# Sheet1.net
KiCad netlist of a schematic drawn in Altium Designer
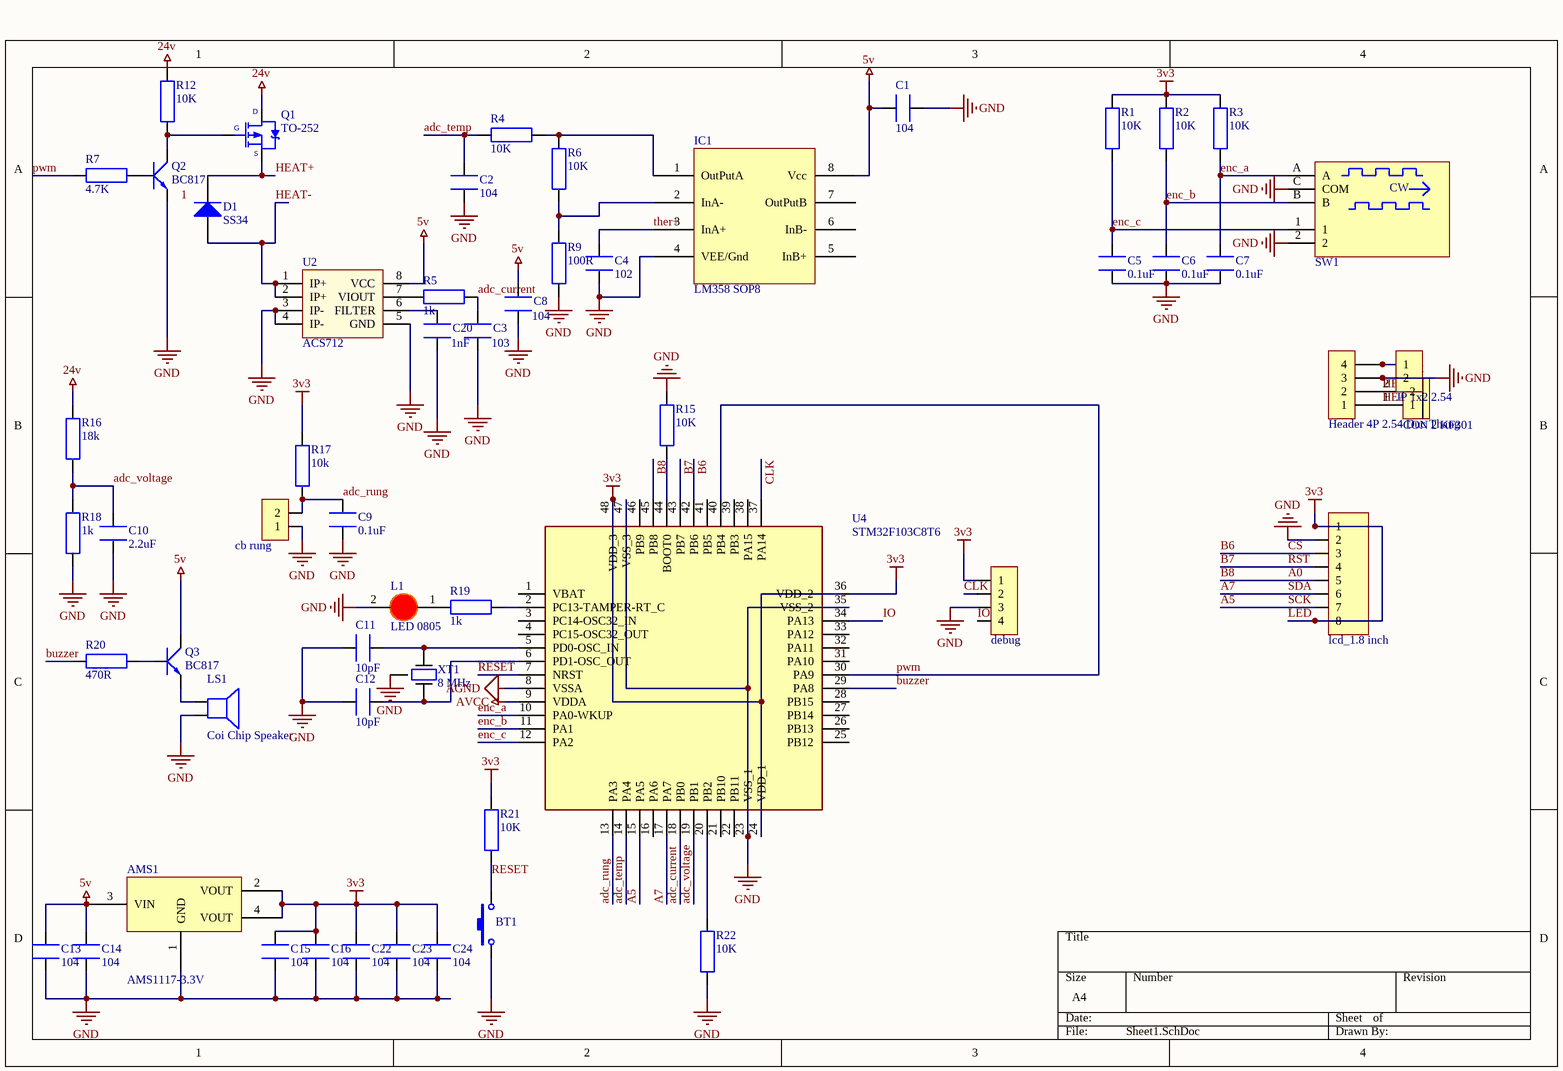
[diagram p0: Sheet1.SchDoc]

(export (version "E")
  (design (tool "Eeschema 10.0.6"))
  (components
    (comp (ref "AMS1")
      (value "AMS1117-3.3V")
      (footprint "SOT223")
      (description "Dán")
      (libsource (lib "Altium_Lib_by_KhueNguyenCreator") (part "AMS1117 SMD"))
    )
    (comp (ref "BT1")
      (value "Nut Nhan 2 Chan SMD 3x6x2.5")
      (footprint "Nut Nhan 2 Chan SMD 3x6x2.5")
      (libsource (lib "Altium_Lib_by_KhueNguyenCreator") (part "Nut Nhan 2 Chan SMD 3x6x2.5"))
    )
    (comp (ref "C1")
      (value "104")
      (footprint "CAPC1608X09L")
      (description "CAP CER 0.1UF 50V X7R 0603")
      (fields
        (field (name "MANUFACTURER") "Murata Electronics North America")
        (field (name "MANUFACTURER PART NUMBER") "GRM188R71H104KA93D")
      )
      (libsource (lib "two_ax_PCB") (part "GRM188R71H104KA93D"))
    )
    (comp (ref "C2")
      (value "104")
      (footprint "CAPC1608X09L")
      (description "CAP CER 0.1UF 50V X7R 0603")
      (fields
        (field (name "MANUFACTURER") "Murata Electronics North America")
        (field (name "MANUFACTURER PART NUMBER") "GRM188R71H104KA93D")
      )
      (libsource (lib "two_ax_PCB") (part "GRM188R71H104KA93D"))
    )
    (comp (ref "C3")
      (value "103")
      (footprint "CAPC1608X09L")
      (description "CAP CER 0.1UF 50V X7R 0603")
      (fields
        (field (name "MANUFACTURER") "Murata Electronics North America")
        (field (name "MANUFACTURER PART NUMBER") "GRM188R71H104KA93D")
      )
      (libsource (lib "two_ax_PCB") (part "GRM188R71H104KA93D"))
    )
    (comp (ref "C4")
      (value "102")
      (footprint "CAPC1608X09L")
      (description "CAP CER 0.1UF 50V X7R 0603")
      (fields
        (field (name "MANUFACTURER") "Murata Electronics North America")
        (field (name "MANUFACTURER PART NUMBER") "GRM188R71H104KA93D")
      )
      (libsource (lib "two_ax_PCB") (part "GRM188R71H104KA93D"))
    )
    (comp (ref "C5")
      (value "0.1uF")
      (footprint "CAPC1608X09L")
      (description "CAP CER 0.1UF 50V X7R 0603")
      (fields
        (field (name "MANUFACTURER") "Murata Electronics North America")
        (field (name "MANUFACTURER PART NUMBER") "GRM188R71H104KA93D")
      )
      (libsource (lib "two_ax_PCB") (part "GRM188R71H104KA93D"))
    )
    (comp (ref "C6")
      (value "0.1uF")
      (footprint "CAPC1608X09L")
      (description "CAP CER 0.1UF 50V X7R 0603")
      (fields
        (field (name "MANUFACTURER") "Murata Electronics North America")
        (field (name "MANUFACTURER PART NUMBER") "GRM188R71H104KA93D")
      )
      (libsource (lib "two_ax_PCB") (part "GRM188R71H104KA93D"))
    )
    (comp (ref "C7")
      (value "0.1uF")
      (footprint "CAPC1608X09L")
      (description "CAP CER 0.1UF 50V X7R 0603")
      (fields
        (field (name "MANUFACTURER") "Murata Electronics North America")
        (field (name "MANUFACTURER PART NUMBER") "GRM188R71H104KA93D")
      )
      (libsource (lib "two_ax_PCB") (part "GRM188R71H104KA93D"))
    )
    (comp (ref "C8")
      (value "104")
      (footprint "CAPC1608X09L")
      (description "CAP CER 0.1UF 50V X7R 0603")
      (fields
        (field (name "MANUFACTURER") "Murata Electronics North America")
        (field (name "MANUFACTURER PART NUMBER") "GRM188R71H104KA93D")
      )
      (libsource (lib "two_ax_PCB") (part "GRM188R71H104KA93D"))
    )
    (comp (ref "C9")
      (value "0.1uF")
      (footprint "CAPC1608X09L")
      (description "CAP CER 0.1UF 50V X7R 0603")
      (fields
        (field (name "MANUFACTURER") "Murata Electronics North America")
        (field (name "MANUFACTURER PART NUMBER") "GRM188R71H104KA93D")
      )
      (libsource (lib "two_ax_PCB") (part "GRM188R71H104KA93D"))
    )
    (comp (ref "C10")
      (value "2.2uF")
      (footprint "CAPC1608X09L")
      (description "CAP CER 0.1UF 50V X7R 0603")
      (fields
        (field (name "MANUFACTURER") "Murata Electronics North America")
        (field (name "MANUFACTURER PART NUMBER") "GRM188R71H104KA93D")
      )
      (libsource (lib "two_ax_PCB") (part "GRM188R71H104KA93D"))
    )
    (comp (ref "C11")
      (value "10pF")
      (footprint "CAPC1608X09L")
      (description "CAP CER 0.1UF 50V X7R 0603")
      (fields
        (field (name "MANUFACTURER") "Murata Electronics North America")
        (field (name "MANUFACTURER PART NUMBER") "GRM188R71H104KA93D")
      )
      (libsource (lib "two_ax_PCB") (part "GRM188R71H104KA93D"))
    )
    (comp (ref "C12")
      (value "10pF")
      (footprint "CAPC1608X09L")
      (description "CAP CER 0.1UF 50V X7R 0603")
      (fields
        (field (name "MANUFACTURER") "Murata Electronics North America")
        (field (name "MANUFACTURER PART NUMBER") "GRM188R71H104KA93D")
      )
      (libsource (lib "two_ax_PCB") (part "GRM188R71H104KA93D"))
    )
    (comp (ref "C13")
      (value "104")
      (footprint "CAPC1608X09L")
      (description "CAP CER 0.1UF 50V X7R 0603")
      (fields
        (field (name "MANUFACTURER") "Murata Electronics North America")
        (field (name "MANUFACTURER PART NUMBER") "GRM188R71H104KA93D")
      )
      (libsource (lib "two_ax_PCB") (part "GRM188R71H104KA93D"))
    )
    (comp (ref "C14")
      (value "104")
      (footprint "CAPC1608X09L")
      (description "CAP CER 0.1UF 50V X7R 0603")
      (fields
        (field (name "MANUFACTURER") "Murata Electronics North America")
        (field (name "MANUFACTURER PART NUMBER") "GRM188R71H104KA93D")
      )
      (libsource (lib "two_ax_PCB") (part "GRM188R71H104KA93D"))
    )
    (comp (ref "C15")
      (value "104")
      (footprint "CAPC1608X09L")
      (description "CAP CER 0.1UF 50V X7R 0603")
      (fields
        (field (name "MANUFACTURER") "Murata Electronics North America")
        (field (name "MANUFACTURER PART NUMBER") "GRM188R71H104KA93D")
      )
      (libsource (lib "two_ax_PCB") (part "GRM188R71H104KA93D"))
    )
    (comp (ref "C16")
      (value "104")
      (footprint "CAPC1608X09L")
      (description "CAP CER 0.1UF 50V X7R 0603")
      (fields
        (field (name "MANUFACTURER") "Murata Electronics North America")
        (field (name "MANUFACTURER PART NUMBER") "GRM188R71H104KA93D")
      )
      (libsource (lib "two_ax_PCB") (part "GRM188R71H104KA93D"))
    )
    (comp (ref "C20")
      (value "1nF")
      (footprint "CAPC1608X09L")
      (description "CAP CER 0.1UF 50V X7R 0603")
      (fields
        (field (name "MANUFACTURER") "Murata Electronics North America")
        (field (name "MANUFACTURER PART NUMBER") "GRM188R71H104KA93D")
      )
      (libsource (lib "two_ax_PCB") (part "GRM188R71H104KA93D"))
    )
    (comp (ref "C22")
      (value "104")
      (footprint "CAPC1608X09L")
      (description "CAP CER 0.1UF 50V X7R 0603")
      (fields
        (field (name "MANUFACTURER") "Murata Electronics North America")
        (field (name "MANUFACTURER PART NUMBER") "GRM188R71H104KA93D")
      )
      (libsource (lib "two_ax_PCB") (part "GRM188R71H104KA93D"))
    )
    (comp (ref "C23")
      (value "104")
      (footprint "CAPC1608X09L")
      (description "CAP CER 0.1UF 50V X7R 0603")
      (fields
        (field (name "MANUFACTURER") "Murata Electronics North America")
        (field (name "MANUFACTURER PART NUMBER") "GRM188R71H104KA93D")
      )
      (libsource (lib "two_ax_PCB") (part "GRM188R71H104KA93D"))
    )
    (comp (ref "C24")
      (value "104")
      (footprint "CAPC1608X09L")
      (description "CAP CER 0.1UF 50V X7R 0603")
      (fields
        (field (name "MANUFACTURER") "Murata Electronics North America")
        (field (name "MANUFACTURER PART NUMBER") "GRM188R71H104KA93D")
      )
      (libsource (lib "two_ax_PCB") (part "GRM188R71H104KA93D"))
    )
    (comp (ref "D1")
      (value "SS34")
      (footprint "DIODE SMA")
      (description "Dán")
      (libsource (lib "Altium_Lib_by_KhueNguyenCreator") (part "Diode SS34 ( 1N5822 )"))
    )
    (comp (ref "H1")
      (value "Header 4P 2.54 Duc Thang")
      (footprint "XH2.54M-4")
      (description "Cắm")
      (libsource (lib "Altium_Lib_by_KhueNguyenCreator") (part "Header 4P 2.54 Duc Thang"))
    )
    (comp (ref "IC1")
      (value "LM358 SOP8")
      (footprint "SOP 8")
      (description "Dán")
      (libsource (lib "Altium_Lib_by_KhueNguyenCreator") (part "LM358 SOP8"))
    )
    (comp (ref "JP1")
      (value "debug")
      (footprint "JP 1x4 DT")
      (description "Cắm")
      (libsource (lib "Altium_Lib_by_KhueNguyenCreator") (part "JP 1x4 2.54 Duc Thang"))
    )
    (comp (ref "JP2")
      (value "JP 1x2 2.54")
      (footprint "JP 1x2 DT")
      (description "Cắm")
      (libsource (lib "") (part "JP 1x2 2.54 Duc Thang_1"))
    )
    (comp (ref "JP3")
      (value "cb rung")
      (footprint "JP 1x2 DT")
      (description "Cắm")
      (libsource (lib "Altium_Lib_by_KhueNguyenCreator") (part "JP 1x2 2.54 Duc Thang"))
    )
    (comp (ref "JP4")
      (value "lcd_1.8 inch")
      (footprint "JP 1x8 DT")
      (description "Cắm")
      (libsource (lib "Altium_Lib_by_KhueNguyenCreator") (part "JP 1x8 2.54 Duc Thang"))
    )
    (comp (ref "KF2")
      (value "CON 2 KF301")
      (footprint "Con 2 KF301 5.08")
      (description "Cắm")
      (libsource (lib "Altium_Lib_by_KhueNguyenCreator") (part "CON 2 KF301"))
    )
    (comp (ref "L1")
      (value "LED 0805")
      (footprint "LED-0805-Red")
      (description "Dán")
      (libsource (lib "Altium_Lib_by_KhueNguyenCreator") (part "LED 0805 Do"))
    )
    (comp (ref "LS1")
      (value "Coi Chip Speaker")
      (footprint "Coi Chip Speacker")
      (description "Còi chip")
      (libsource (lib "Altium_Lib_by_KhueNguyenCreator") (part "Coi Chip Speaker"))
    )
    (comp (ref "Q1")
      (value "TO-252")
      (footprint "TO-252-3_L6.6-W6.1-P4.57-LS9.9-BR-CW")
      (description "P-Channel Power MOSFET")
      (fields (field (name "PUBLISHER") "Altium Limited"))
      (libsource (lib "Altium_Lib_by_KhueNguyenCreator") (part "FET AO D409"))
    )
    (comp (ref "Q2")
      (value "BC817")
      (footprint "SOT-23")
      (description "SOT-23 - C8658")
      (libsource (lib "Altium_Lib_by_KhueNguyenCreator") (part "Trans BC817"))
    )
    (comp (ref "Q3")
      (value "BC817")
      (footprint "SOT-23")
      (description "SOT-23 - C8658")
      (libsource (lib "Altium_Lib_by_KhueNguyenCreator") (part "Trans BC817"))
    )
    (comp (ref "R1")
      (value "10K")
      (footprint "RESC1608X55N")
      (description "RES SMD 10K OHM 1% 1/10W 0603")
      (fields
        (field (name "MANUFACTURER") "Yageo")
        (field (name "MANUFACTURER PART NUMBER") "RC0603FR-0710KL")
      )
      (libsource (lib "two_ax_PCB") (part "RC0603FR-0710KL"))
    )
    (comp (ref "R2")
      (value "10K")
      (footprint "RESC1608X55N")
      (description "RES SMD 10K OHM 1% 1/10W 0603")
      (fields
        (field (name "MANUFACTURER") "Yageo")
        (field (name "MANUFACTURER PART NUMBER") "RC0603FR-0710KL")
      )
      (libsource (lib "two_ax_PCB") (part "RC0603FR-0710KL"))
    )
    (comp (ref "R3")
      (value "10K")
      (footprint "RESC1608X55N")
      (description "RES SMD 10K OHM 1% 1/10W 0603")
      (fields
        (field (name "MANUFACTURER") "Yageo")
        (field (name "MANUFACTURER PART NUMBER") "RC0603FR-0710KL")
      )
      (libsource (lib "two_ax_PCB") (part "RC0603FR-0710KL"))
    )
    (comp (ref "R4")
      (value "10K")
      (footprint "RESC1608X55N")
      (description "RES SMD 10K OHM 1% 1/10W 0603")
      (fields
        (field (name "MANUFACTURER") "Yageo")
        (field (name "MANUFACTURER PART NUMBER") "RC0603FR-0710KL")
      )
      (libsource (lib "two_ax_PCB") (part "RC0603FR-0710KL"))
    )
    (comp (ref "R5")
      (value "1k")
      (footprint "RESC1608X55N")
      (description "RES SMD 2.2 OHM 1% 1/10W 0603")
      (fields
        (field (name "MANUFACTURER") "Yageo")
        (field (name "MANUFACTURER PART NUMBER") "RC0603FR-072R2L")
      )
      (libsource (lib "two_ax_PCB") (part "RC0603FR-072R2L"))
    )
    (comp (ref "R6")
      (value "10K")
      (footprint "RESC1608X55N")
      (description "RES SMD 10K OHM 1% 1/10W 0603")
      (fields
        (field (name "MANUFACTURER") "Yageo")
        (field (name "MANUFACTURER PART NUMBER") "RC0603FR-0710KL")
      )
      (libsource (lib "two_ax_PCB") (part "RC0603FR-0710KL"))
    )
    (comp (ref "R7")
      (value "4.7K")
      (footprint "RESC1608X55N")
      (description "RES SMD 47K OHM 1% 1/10W 0603")
      (fields
        (field (name "MANUFACTURER") "Yageo")
        (field (name "MANUFACTURER PART NUMBER") "RC0603FR-0747KL")
      )
      (libsource (lib "two_ax_PCB") (part "RC0603FR-0747KL"))
    )
    (comp (ref "R9")
      (value "100R")
      (footprint "RESC1608X55N")
      (description "RES SMD 10K OHM 1% 1/10W 0603")
      (fields
        (field (name "MANUFACTURER") "Yageo")
        (field (name "MANUFACTURER PART NUMBER") "RC0603FR-0710KL")
      )
      (libsource (lib "two_ax_PCB") (part "RC0603FR-0710KL"))
    )
    (comp (ref "R12")
      (value "10K")
      (footprint "RESC1608X55N")
      (description "RES SMD 22 OHM 1% 1/10W 0603")
      (fields
        (field (name "MANUFACTURER") "Yageo")
        (field (name "MANUFACTURER PART NUMBER") "RC0603FR-0722RL")
      )
      (libsource (lib "two_ax_PCB") (part "RC0603FR-0722RL"))
    )
    (comp (ref "R15")
      (value "10K")
      (footprint "RESC1608X55N")
      (description "RES SMD 10K OHM 1% 1/10W 0603")
      (fields
        (field (name "MANUFACTURER") "Yageo")
        (field (name "MANUFACTURER PART NUMBER") "RC0603FR-0710KL")
      )
      (libsource (lib "two_ax_PCB") (part "RC0603FR-0710KL"))
    )
    (comp (ref "R16")
      (value "18k")
      (footprint "RESC1608X55N")
      (description "RES SMD 2.2 OHM 1% 1/10W 0603")
      (fields
        (field (name "MANUFACTURER") "Yageo")
        (field (name "MANUFACTURER PART NUMBER") "RC0603FR-072R2L")
      )
      (libsource (lib "two_ax_PCB") (part "RC0603FR-072R2L"))
    )
    (comp (ref "R17")
      (value "10k")
      (footprint "RESC1608X55N")
      (description "RES SMD 2.2 OHM 1% 1/10W 0603")
      (fields
        (field (name "MANUFACTURER") "Yageo")
        (field (name "MANUFACTURER PART NUMBER") "RC0603FR-072R2L")
      )
      (libsource (lib "two_ax_PCB") (part "RC0603FR-072R2L"))
    )
    (comp (ref "R18")
      (value "1k")
      (footprint "RESC1608X55N")
      (description "RES SMD 2.2 OHM 1% 1/10W 0603")
      (fields
        (field (name "MANUFACTURER") "Yageo")
        (field (name "MANUFACTURER PART NUMBER") "RC0603FR-072R2L")
      )
      (libsource (lib "two_ax_PCB") (part "RC0603FR-072R2L"))
    )
    (comp (ref "R19")
      (value "1k")
      (footprint "RESC1608X55N")
      (description "RES SMD 10K OHM 1% 1/10W 0603")
      (fields
        (field (name "MANUFACTURER") "Yageo")
        (field (name "MANUFACTURER PART NUMBER") "RC0603FR-0710KL")
      )
      (libsource (lib "two_ax_PCB") (part "RC0603FR-0710KL"))
    )
    (comp (ref "R20")
      (value "470R")
      (footprint "RESC1608X55N")
      (description "RES SMD 10K OHM 1% 1/10W 0603")
      (fields
        (field (name "MANUFACTURER") "Yageo")
        (field (name "MANUFACTURER PART NUMBER") "RC0603FR-0710KL")
      )
      (libsource (lib "two_ax_PCB") (part "RC0603FR-0710KL"))
    )
    (comp (ref "R21")
      (value "10K")
      (footprint "RESC1608X55N")
      (description "RES SMD 10K OHM 1% 1/10W 0603")
      (fields
        (field (name "MANUFACTURER") "Yageo")
        (field (name "MANUFACTURER PART NUMBER") "RC0603FR-0710KL")
      )
      (libsource (lib "two_ax_PCB") (part "RC0603FR-0710KL"))
    )
    (comp (ref "R22")
      (value "10K")
      (footprint "RESC1608X55N")
      (description "RES SMD 10K OHM 1% 1/10W 0603")
      (fields
        (field (name "MANUFACTURER") "Yageo")
        (field (name "MANUFACTURER PART NUMBER") "RC0603FR-0710KL")
      )
      (libsource (lib "two_ax_PCB") (part "RC0603FR-0710KL"))
    )
    (comp (ref "SW1")
      (value "482024764004")
      (footprint "482024764004")
      (fields (field (name "MANUFACTURER") "Wurth Elektronik"))
      (libsource (lib "Altium_WS-ENTV_rev23a") (part "482024764004"))
    )
    (comp (ref "U2")
      (value "ACS712")
      (footprint "SOIC8_50_328_25X90_SMT")
      (description "ACS712 Hall Effect-Based Linear Current Sensor")
      (libsource (lib "Altium_Lib_by_KhueNguyenCreator") (part "ACS712"))
    )
    (comp (ref "U4")
      (value "STM32F103C8T6")
      (footprint "LQFP-48_19.6_393_58X11_SMD")
      (description "ARM® Cortex®-M3 STM32F1 Microcontroller IC 32-Bit 72MHz 64KB (64K x 8) FLASH 48-LQFP (7x7)")
      (fields (field (name "MANUFACTURER") "STMicroelectronics"))
      (libsource (lib "Altium_Lib_by_KhueNguyenCreator") (part "IC_STM32F103C8T6"))
    )
    (comp (ref "XT1")
      (value "8 MHz")
      (footprint "DFN220P320X110-4N")
      (description "Crystal 8MHz ±10ppm 10pF 200 Ohm -10°C ~ 60°C Surface Mount 4-SMD, No Lead (DFN, LCC)")
      (fields
        (field (name "MANUFACTURER") "Abracon LLC")
        (field (name "MANUFACTURER PART NUMBER") "ABM3B-8.000MHZ-10-1-U-T")
      )
      (libsource (lib "two_ax_PCB") (part "ABM3B-8.000MHZ-10-1-U-T"))
    )
  )
  (nets
    (net (code "2") (name "/A0") (class "Default")
      (node (ref "JP4") (pin "5") (pinfunction "5_5") (pintype "passive"))
      (node (ref "U4") (pin "45") (pinfunction "PB8_45") (pintype "passive"))
    )
    (net (code "3") (name "/A5") (class "Default")
      (node (ref "JP4") (pin "7") (pinfunction "7_7") (pintype "passive"))
      (node (ref "U4") (pin "15") (pinfunction "PA5_15") (pintype "passive"))
    )
    (net (code "4") (name "/A7") (class "Default")
      (node (ref "JP4") (pin "6") (pinfunction "6_6") (pintype "passive"))
      (node (ref "U4") (pin "17") (pinfunction "PA7_17") (pintype "passive"))
    )
    (net (code "5") (name "/B6") (class "Default")
      (node (ref "JP4") (pin "3") (pinfunction "3_3") (pintype "passive"))
      (node (ref "U4") (pin "42") (pinfunction "PB6_42") (pintype "passive"))
    )
    (net (code "6") (name "/B7") (class "Default")
      (node (ref "JP4") (pin "4") (pinfunction "4_4") (pintype "passive"))
      (node (ref "U4") (pin "43") (pinfunction "PB7_43") (pintype "passive"))
    )
    (net (code "7") (name "/CLK") (class "Default")
      (node (ref "JP1") (pin "2") (pinfunction "2_2") (pintype "passive"))
      (node (ref "U4") (pin "37") (pinfunction "PA14_37") (pintype "passive"))
    )
    (net (code "8") (name "/HEAT+") (class "Default")
      (node (ref "D1") (pin "2") (pinfunction "K_2") (pintype "passive"))
      (node (ref "H1") (pin "2") (pinfunction "2_2") (pintype "passive"))
      (node (ref "KF2") (pin "2") (pinfunction "2_2") (pintype "passive"))
      (node (ref "Q1") (pin "3") (pinfunction "S_3") (pintype "passive"))
    )
    (net (code "9") (name "/HEAT-") (class "Default")
      (node (ref "D1") (pin "1") (pinfunction "A_1") (pintype "passive"))
      (node (ref "H1") (pin "1") (pinfunction "1_1") (pintype "passive"))
      (node (ref "KF2") (pin "1") (pinfunction "1_1") (pintype "passive"))
      (node (ref "U2") (pin "1") (pinfunction "IP+_1") (pintype "passive"))
      (node (ref "U2") (pin "2") (pinfunction "IP+_2") (pintype "passive"))
    )
    (net (code "10") (name "/IO") (class "Default")
      (node (ref "JP1") (pin "4") (pinfunction "4_4") (pintype "passive"))
      (node (ref "U4") (pin "34") (pinfunction "PA13_34") (pintype "passive"))
    )
    (net (code "11") (name "/RESET") (class "Default")
      (node (ref "BT1") (pin "2") (pinfunction "2_2") (pintype "passive"))
      (node (ref "R21") (pin "1") (pinfunction "0_1") (pintype "passive"))
      (node (ref "U4") (pin "7") (pinfunction "NRST_7") (pintype "passive"))
    )
    (net (code "12") (name "/adc_current") (class "Default")
      (node (ref "C3") (pin "1") (pinfunction "1_1") (pintype "passive"))
      (node (ref "R5") (pin "2") (pinfunction "0_2") (pintype "passive"))
      (node (ref "U4") (pin "18") (pinfunction "PB0_18") (pintype "passive"))
    )
    (net (code "13") (name "/adc_rung") (class "Default")
      (node (ref "C9") (pin "1") (pinfunction "1_1") (pintype "passive"))
      (node (ref "JP3") (pin "2") (pinfunction "2_2") (pintype "passive"))
      (node (ref "R17") (pin "2") (pinfunction "0_2") (pintype "passive"))
      (node (ref "U4") (pin "13") (pinfunction "PA3_13") (pintype "passive"))
    )
    (net (code "14") (name "/adc_temp") (class "Default")
      (node (ref "C2") (pin "1") (pinfunction "1_1") (pintype "passive"))
      (node (ref "R4") (pin "2") (pinfunction "0_2") (pintype "passive"))
      (node (ref "U4") (pin "14") (pinfunction "PA4_14") (pintype "passive"))
    )
    (net (code "15") (name "/adc_voltage") (class "Default")
      (node (ref "C10") (pin "1") (pinfunction "1_1") (pintype "passive"))
      (node (ref "R16") (pin "2") (pinfunction "0_2") (pintype "passive"))
      (node (ref "R18") (pin "1") (pinfunction "0_1") (pintype "passive"))
      (node (ref "U4") (pin "19") (pinfunction "PB1_19") (pintype "passive"))
    )
    (net (code "16") (name "/buzzer") (class "Default")
      (node (ref "R20") (pin "2") (pinfunction "0_2") (pintype "passive"))
      (node (ref "U4") (pin "29") (pinfunction "PA8_29") (pintype "passive"))
    )
    (net (code "17") (name "/enc_a") (class "Default")
      (node (ref "C7") (pin "2") (pinfunction "2_2") (pintype "passive"))
      (node (ref "R3") (pin "1") (pinfunction "0_1") (pintype "passive"))
      (node (ref "SW1") (pin "A") (pinfunction "A_A") (pintype "passive"))
      (node (ref "U4") (pin "10") (pinfunction "PA0-WKUP_10") (pintype "passive"))
    )
    (net (code "18") (name "/enc_b") (class "Default")
      (node (ref "C6") (pin "2") (pinfunction "2_2") (pintype "passive"))
      (node (ref "R2") (pin "1") (pinfunction "0_1") (pintype "passive"))
      (node (ref "SW1") (pin "B") (pinfunction "B_B") (pintype "passive"))
      (node (ref "U4") (pin "11") (pinfunction "PA1_11") (pintype "passive"))
    )
    (net (code "19") (name "/enc_c") (class "Default")
      (node (ref "C5") (pin "2") (pinfunction "2_2") (pintype "passive"))
      (node (ref "R1") (pin "1") (pinfunction "0_1") (pintype "passive"))
      (node (ref "SW1") (pin "1") (pinfunction "1_1") (pintype "passive"))
      (node (ref "U4") (pin "12") (pinfunction "PA2_12") (pintype "passive"))
    )
    (net (code "20") (name "/pwm") (class "Default")
      (node (ref "R7") (pin "2") (pinfunction "0_2") (pintype "passive"))
      (node (ref "U4") (pin "30") (pinfunction "PA9_30") (pintype "passive"))
      (node (ref "U4") (pin "40") (pinfunction "PB4_40") (pintype "passive"))
    )
    (net (code "21") (name "/ther+") (class "Default")
      (node (ref "C4") (pin "2") (pinfunction "2_2") (pintype "passive"))
      (node (ref "H1") (pin "4") (pinfunction "4_4") (pintype "passive"))
      (node (ref "IC1") (pin "3") (pinfunction "InA+_3") (pintype "passive"))
      (node (ref "JP2") (pin "1") (pinfunction "1_1") (pintype "passive"))
    )
    (net (code "22") (name "3v3") (class "Default")
      (node (ref "AMS1") (pin "2") (pinfunction "VOUT_2") (pintype "passive"))
      (node (ref "AMS1") (pin "4") (pinfunction "VOUT_4") (pintype "passive"))
      (node (ref "C15") (pin "2") (pinfunction "2_2") (pintype "passive"))
      (node (ref "C16") (pin "2") (pinfunction "2_2") (pintype "passive"))
      (node (ref "C22") (pin "2") (pinfunction "2_2") (pintype "passive"))
      (node (ref "C23") (pin "2") (pinfunction "2_2") (pintype "passive"))
      (node (ref "C24") (pin "2") (pinfunction "2_2") (pintype "passive"))
      (node (ref "JP1") (pin "1") (pinfunction "1_1") (pintype "passive"))
      (node (ref "JP4") (pin "1") (pinfunction "1_1") (pintype "passive"))
      (node (ref "JP4") (pin "8") (pinfunction "8_8") (pintype "passive"))
      (node (ref "R1") (pin "2") (pinfunction "0_2") (pintype "passive"))
      (node (ref "R17") (pin "1") (pinfunction "0_1") (pintype "passive"))
      (node (ref "R2") (pin "2") (pinfunction "0_2") (pintype "passive"))
      (node (ref "R21") (pin "2") (pinfunction "0_2") (pintype "passive"))
      (node (ref "R3") (pin "2") (pinfunction "0_2") (pintype "passive"))
      (node (ref "U4") (pin "24") (pinfunction "VDD_1_24") (pintype "passive"))
      (node (ref "U4") (pin "36") (pinfunction "VDD_2_36") (pintype "passive"))
      (node (ref "U4") (pin "48") (pinfunction "VDD_3_48") (pintype "passive"))
    )
    (net (code "23") (name "5v") (class "Default")
      (node (ref "AMS1") (pin "3") (pinfunction "VIN_3") (pintype "passive"))
      (node (ref "C1") (pin "2") (pinfunction "2_2") (pintype "passive"))
      (node (ref "C13") (pin "2") (pinfunction "2_2") (pintype "passive"))
      (node (ref "C14") (pin "2") (pinfunction "2_2") (pintype "passive"))
      (node (ref "C8") (pin "1") (pinfunction "1_1") (pintype "passive"))
      (node (ref "IC1") (pin "8") (pinfunction "Vcc_8") (pintype "passive"))
      (node (ref "Q3") (pin "3") (pinfunction "C_3") (pintype "passive"))
      (node (ref "U2") (pin "8") (pinfunction "VCC_8") (pintype "passive"))
    )
    (net (code "24") (name "24v") (class "Default")
      (node (ref "Q1") (pin "2") (pinfunction "D_2") (pintype "passive"))
      (node (ref "R12") (pin "2") (pinfunction "0_2") (pintype "passive"))
      (node (ref "R16") (pin "1") (pinfunction "0_1") (pintype "passive"))
    )
    (net (code "25") (name "AGND") (class "Default")
      (node (ref "U4") (pin "8") (pinfunction "VSSA_8") (pintype "passive"))
    )
    (net (code "26") (name "AVCC") (class "Default")
      (node (ref "U4") (pin "9") (pinfunction "VDDA_9") (pintype "passive"))
    )
    (net (code "27") (name "GND") (class "Default")
      (node (ref "AMS1") (pin "1") (pinfunction "GND_1") (pintype "passive"))
      (node (ref "BT1") (pin "1") (pinfunction "1_1") (pintype "passive"))
      (node (ref "C1") (pin "1") (pinfunction "1_1") (pintype "passive"))
      (node (ref "C10") (pin "2") (pinfunction "2_2") (pintype "passive"))
      (node (ref "C11") (pin "1") (pinfunction "1_1") (pintype "passive"))
      (node (ref "C12") (pin "1") (pinfunction "1_1") (pintype "passive"))
      (node (ref "C13") (pin "1") (pinfunction "1_1") (pintype "passive"))
      (node (ref "C14") (pin "1") (pinfunction "1_1") (pintype "passive"))
      (node (ref "C15") (pin "1") (pinfunction "1_1") (pintype "passive"))
      (node (ref "C16") (pin "1") (pinfunction "1_1") (pintype "passive"))
      (node (ref "C2") (pin "2") (pinfunction "2_2") (pintype "passive"))
      (node (ref "C20") (pin "2") (pinfunction "2_2") (pintype "passive"))
      (node (ref "C22") (pin "1") (pinfunction "1_1") (pintype "passive"))
      (node (ref "C23") (pin "1") (pinfunction "1_1") (pintype "passive"))
      (node (ref "C24") (pin "1") (pinfunction "1_1") (pintype "passive"))
      (node (ref "C3") (pin "2") (pinfunction "2_2") (pintype "passive"))
      (node (ref "C4") (pin "1") (pinfunction "1_1") (pintype "passive"))
      (node (ref "C5") (pin "1") (pinfunction "1_1") (pintype "passive"))
      (node (ref "C6") (pin "1") (pinfunction "1_1") (pintype "passive"))
      (node (ref "C7") (pin "1") (pinfunction "1_1") (pintype "passive"))
      (node (ref "C8") (pin "2") (pinfunction "2_2") (pintype "passive"))
      (node (ref "C9") (pin "2") (pinfunction "2_2") (pintype "passive"))
      (node (ref "H1") (pin "3") (pinfunction "3_3") (pintype "passive"))
      (node (ref "IC1") (pin "4") (pinfunction "VEE/Gnd_4") (pintype "passive"))
      (node (ref "JP1") (pin "3") (pinfunction "3_3") (pintype "passive"))
      (node (ref "JP2") (pin "2") (pinfunction "2_2") (pintype "passive"))
      (node (ref "JP3") (pin "1") (pinfunction "1_1") (pintype "passive"))
      (node (ref "JP4") (pin "2") (pinfunction "2_2") (pintype "passive"))
      (node (ref "L1") (pin "2") (pinfunction "K_2") (pintype "passive"))
      (node (ref "LS1") (pin "2") (pinfunction "2_2") (pintype "passive"))
      (node (ref "Q2") (pin "2") (pinfunction "E_2") (pintype "passive"))
      (node (ref "R15") (pin "2") (pinfunction "0_2") (pintype "passive"))
      (node (ref "R18") (pin "2") (pinfunction "0_2") (pintype "passive"))
      (node (ref "R22") (pin "1") (pinfunction "0_1") (pintype "passive"))
      (node (ref "R9") (pin "1") (pinfunction "0_1") (pintype "passive"))
      (node (ref "SW1") (pin "2") (pinfunction "2_2") (pintype "passive"))
      (node (ref "SW1") (pin "C") (pinfunction "COM_C") (pintype "passive"))
      (node (ref "U2") (pin "3") (pinfunction "IP-_3") (pintype "passive"))
      (node (ref "U2") (pin "4") (pinfunction "IP-_4") (pintype "passive"))
      (node (ref "U2") (pin "5") (pinfunction "GND_5") (pintype "passive"))
      (node (ref "U4") (pin "23") (pinfunction "VSS_1_23") (pintype "passive"))
      (node (ref "U4") (pin "35") (pinfunction "VSS_2_35") (pintype "passive"))
      (node (ref "U4") (pin "47") (pinfunction "VSS_3_47") (pintype "passive"))
      (node (ref "XT1") (pin "G") (pintype "passive"))
    )
    (net (code "28") (name "Net-(IC1-InA-)") (class "Default")
      (node (ref "IC1") (pin "2") (pinfunction "InA-_2") (pintype "passive"))
      (node (ref "R6") (pin "1") (pinfunction "0_1") (pintype "passive"))
      (node (ref "R9") (pin "2") (pinfunction "0_2") (pintype "passive"))
    )
    (net (code "29") (name "Net-(IC1-OutPutA)") (class "Default")
      (node (ref "IC1") (pin "1") (pinfunction "OutPutA_1") (pintype "passive"))
      (node (ref "R4") (pin "1") (pinfunction "0_1") (pintype "passive"))
      (node (ref "R6") (pin "2") (pinfunction "0_2") (pintype "passive"))
    )
    (net (code "30") (name "Net-(L1-A)") (class "Default")
      (node (ref "L1") (pin "1") (pinfunction "A_1") (pintype "passive"))
      (node (ref "R19") (pin "2") (pinfunction "0_2") (pintype "passive"))
    )
    (net (code "31") (name "Net-(Q1-G)") (class "Default")
      (node (ref "Q1") (pin "1") (pinfunction "G_1") (pintype "passive"))
      (node (ref "Q2") (pin "3") (pinfunction "C_3") (pintype "passive"))
      (node (ref "R12") (pin "1") (pinfunction "0_1") (pintype "passive"))
    )
    (net (code "32") (name "Net-(Q2-B)") (class "Default")
      (node (ref "Q2") (pin "1") (pinfunction "B_1") (pintype "passive"))
      (node (ref "R7") (pin "1") (pinfunction "0_1") (pintype "passive"))
    )
    (net (code "33") (name "Net-(Q3-B)") (class "Default")
      (node (ref "Q3") (pin "1") (pinfunction "B_1") (pintype "passive"))
      (node (ref "R20") (pin "1") (pinfunction "0_1") (pintype "passive"))
    )
    (net (code "34") (name "Net-(Q3-E)") (class "Default")
      (node (ref "LS1") (pin "1") (pinfunction "1_1") (pintype "passive"))
      (node (ref "Q3") (pin "2") (pinfunction "E_2") (pintype "passive"))
    )
    (net (code "35") (name "Net-(U2-FILTER)") (class "Default")
      (node (ref "C20") (pin "1") (pinfunction "1_1") (pintype "passive"))
      (node (ref "U2") (pin "6") (pinfunction "FILTER_6") (pintype "passive"))
    )
    (net (code "36") (name "Net-(U2-VIOUT)") (class "Default")
      (node (ref "R5") (pin "1") (pinfunction "0_1") (pintype "passive"))
      (node (ref "U2") (pin "7") (pinfunction "VIOUT_7") (pintype "passive"))
    )
    (net (code "37") (name "Net-(U4-BOOT0)") (class "Default")
      (node (ref "R15") (pin "1") (pinfunction "0_1") (pintype "passive"))
      (node (ref "U4") (pin "44") (pinfunction "BOOT0_44") (pintype "passive"))
    )
    (net (code "38") (name "Net-(U4-PB2)") (class "Default")
      (node (ref "R22") (pin "2") (pinfunction "0_2") (pintype "passive"))
      (node (ref "U4") (pin "20") (pinfunction "PB2_20") (pintype "passive"))
    )
    (net (code "39") (name "Net-(U4-PC13-TAMPER-RT_C)") (class "Default")
      (node (ref "R19") (pin "1") (pinfunction "0_1") (pintype "passive"))
      (node (ref "U4") (pin "2") (pinfunction "PC13-TAMPER-RT_C_2") (pintype "passive"))
    )
    (net (code "40") (name "Net-(U4-PD0-OSC_IN)") (class "Default")
      (node (ref "C11") (pin "2") (pinfunction "2_2") (pintype "passive"))
      (node (ref "U4") (pin "5") (pinfunction "PD0-OSC_IN_5") (pintype "passive"))
      (node (ref "XT1") (pin "1") (pintype "passive"))
    )
    (net (code "41") (name "Net-(U4-PD1-OSC_OUT)") (class "Default")
      (node (ref "C12") (pin "2") (pinfunction "2_2") (pintype "passive"))
      (node (ref "U4") (pin "6") (pinfunction "PD1-OSC_OUT_6") (pintype "passive"))
      (node (ref "XT1") (pin "3") (pintype "passive"))
    )
    (net (code "42") (name "unconnected-(IC1-InB+-Pad5)") (class "Default")
      (node (ref "IC1") (pin "5") (pinfunction "InB+_5") (pintype "passive"))
    )
    (net (code "43") (name "unconnected-(IC1-InB--Pad6)") (class "Default")
      (node (ref "IC1") (pin "6") (pinfunction "InB-_6") (pintype "passive"))
    )
    (net (code "44") (name "unconnected-(IC1-OutPutB-Pad7)") (class "Default")
      (node (ref "IC1") (pin "7") (pinfunction "OutPutB_7") (pintype "passive"))
    )
    (net (code "45") (name "unconnected-(U4-PA6-Pad16)") (class "Default")
      (node (ref "U4") (pin "16") (pinfunction "PA6_16") (pintype "passive"))
    )
    (net (code "46") (name "unconnected-(U4-PA10-Pad31)") (class "Default")
      (node (ref "U4") (pin "31") (pinfunction "PA10_31") (pintype "passive"))
    )
    (net (code "47") (name "unconnected-(U4-PA11-Pad32)") (class "Default")
      (node (ref "U4") (pin "32") (pinfunction "PA11_32") (pintype "passive"))
    )
    (net (code "48") (name "unconnected-(U4-PA12-Pad33)") (class "Default")
      (node (ref "U4") (pin "33") (pinfunction "PA12_33") (pintype "passive"))
    )
    (net (code "49") (name "unconnected-(U4-PA15-Pad38)") (class "Default")
      (node (ref "U4") (pin "38") (pinfunction "PA15_38") (pintype "passive"))
    )
    (net (code "50") (name "unconnected-(U4-PB3-Pad39)") (class "Default")
      (node (ref "U4") (pin "39") (pinfunction "PB3_39") (pintype "passive"))
    )
    (net (code "51") (name "unconnected-(U4-PB5-Pad41)") (class "Default")
      (node (ref "U4") (pin "41") (pinfunction "PB5_41") (pintype "passive"))
    )
    (net (code "52") (name "unconnected-(U4-PB9-Pad46)") (class "Default")
      (node (ref "U4") (pin "46") (pinfunction "PB9_46") (pintype "passive"))
    )
    (net (code "53") (name "unconnected-(U4-PB10-Pad21)") (class "Default")
      (node (ref "U4") (pin "21") (pinfunction "PB10_21") (pintype "passive"))
    )
    (net (code "54") (name "unconnected-(U4-PB11-Pad22)") (class "Default")
      (node (ref "U4") (pin "22") (pinfunction "PB11_22") (pintype "passive"))
    )
    (net (code "55") (name "unconnected-(U4-PB12-Pad25)") (class "Default")
      (node (ref "U4") (pin "25") (pinfunction "PB12_25") (pintype "passive"))
    )
    (net (code "56") (name "unconnected-(U4-PB13-Pad26)") (class "Default")
      (node (ref "U4") (pin "26") (pinfunction "PB13_26") (pintype "passive"))
    )
    (net (code "57") (name "unconnected-(U4-PB14-Pad27)") (class "Default")
      (node (ref "U4") (pin "27") (pinfunction "PB14_27") (pintype "passive"))
    )
    (net (code "58") (name "unconnected-(U4-PB15-Pad28)") (class "Default")
      (node (ref "U4") (pin "28") (pinfunction "PB15_28") (pintype "passive"))
    )
    (net (code "59") (name "unconnected-(U4-PC14-OSC32_IN-Pad3)") (class "Default")
      (node (ref "U4") (pin "3") (pinfunction "PC14-OSC32_IN_3") (pintype "passive"))
    )
    (net (code "60") (name "unconnected-(U4-PC15-OSC32_OUT-Pad4)") (class "Default")
      (node (ref "U4") (pin "4") (pinfunction "PC15-OSC32_OUT_4") (pintype "passive"))
    )
    (net (code "61") (name "unconnected-(U4-VBAT-Pad1)") (class "Default")
      (node (ref "U4") (pin "1") (pinfunction "VBAT_1") (pintype "passive"))
    )
  )
)
